# MainBoard.net
KiCad netlist of a schematic drawn in Altium Designer
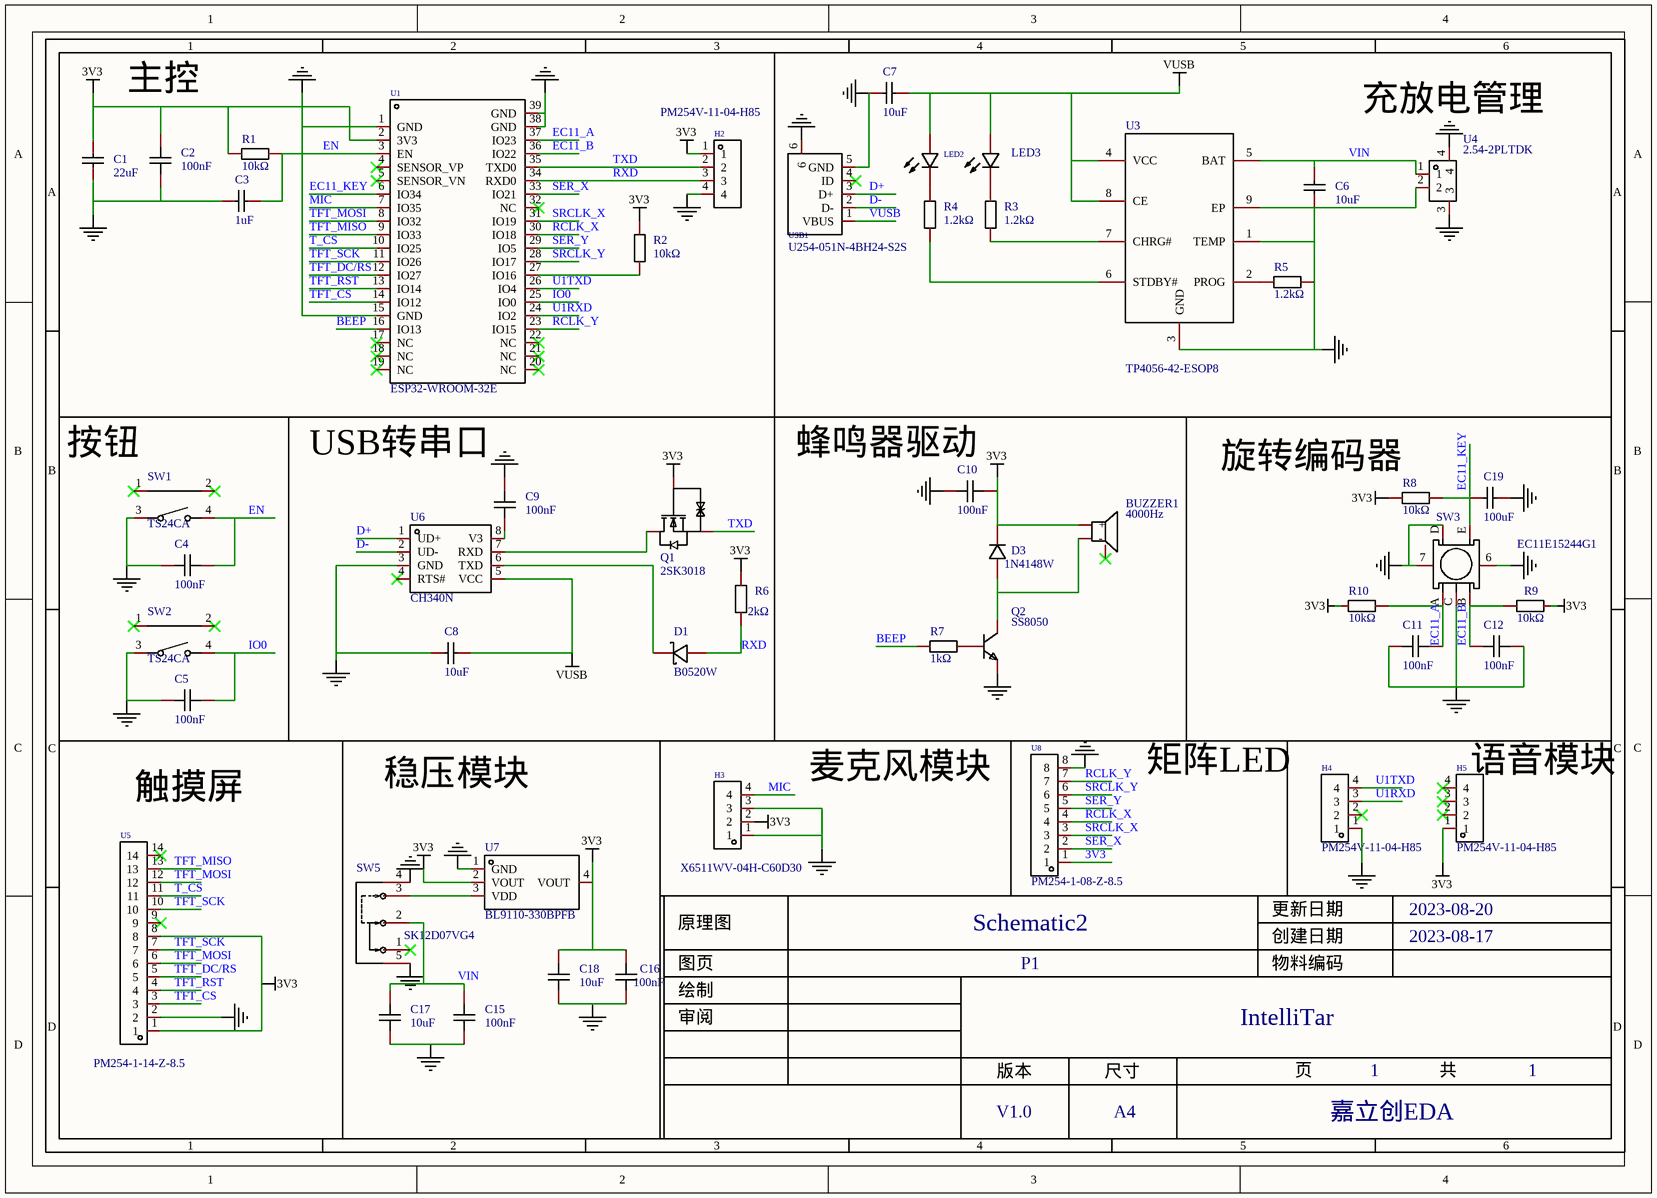
[diagram p0: MainBoard.schdoc]

(export (version "E")
  (design (tool "Eeschema 10.0.6"))
  (components
    (comp (ref "BUZZER1")
      (value "4000Hz")
      (description "驱动方式:无源(外部驱动);构造类型:电磁式;频率:4000Hz;长度:5.2mm;宽度:5.2mm;高度:2.5mm;")
      (fields
        (field (name "NAME") "4000Hz")
        (field (name "MANUFACTURER") "华能")
        (field (name "MANUFACTURER PART") "MLT-5020")
      )
      (libsource (lib "altium-import") (part "root_0_MLT-5020_"))
    )
    (comp (ref "C1")
      (value "22uF")
      (description "容值:22uF;精度:±10%;额定电压:25V;材质(温度系数):X5R;")
      (fields
        (field (name "NAME") "22uF")
        (field (name "MANUFACTURER") "SAMSUNG(三星)")
        (field (name "MANUFACTURER PART") "CL31A226KAHNNNE")
      )
      (libsource (lib "altium-import") (part "root_1_CL31A226KAHNNNE_"))
    )
    (comp (ref "C2")
      (value "100nF")
      (description "容值:100nF;精度:±10%;额定电压:50V;材质(温度系数):X7R;")
      (fields
        (field (name "NAME") "100nF")
        (field (name "MANUFACTURER") "YAGEO(国巨)")
        (field (name "MANUFACTURER PART") "CC0603KRX7R9BB104")
      )
      (libsource (lib "altium-import") (part "root_1_CC0603KRX7R9BB104_"))
    )
    (comp (ref "C3")
      (value "1uF")
      (description "容值:1uF;精度:±10%;额定电压:50V;材质(温度系数):X5R;")
      (fields
        (field (name "NAME") "1uF")
        (field (name "MANUFACTURER") "SAMSUNG(三星)")
        (field (name "MANUFACTURER PART") "CL10A105KB8NNNC")
      )
      (libsource (lib "altium-import") (part "root_0_CL10A105KB8NNNC_"))
    )
    (comp (ref "C4")
      (value "100nF")
      (description "容值:100nF;精度:±10%;额定电压:50V;材质(温度系数):X7R;")
      (fields
        (field (name "NAME") "100nF")
        (field (name "MANUFACTURER") "YAGEO(国巨)")
        (field (name "MANUFACTURER PART") "CC0603KRX7R9BB104")
      )
      (libsource (lib "altium-import") (part "root_0_CC0603KRX7R9BB104_"))
    )
    (comp (ref "C5")
      (value "100nF")
      (description "容值:100nF;精度:±10%;额定电压:50V;材质(温度系数):X7R;")
      (fields
        (field (name "NAME") "100nF")
        (field (name "MANUFACTURER") "YAGEO(国巨)")
        (field (name "MANUFACTURER PART") "CC0603KRX7R9BB104")
      )
      (libsource (lib "altium-import") (part "root_0_CC0603KRX7R9BB104_"))
    )
    (comp (ref "C6")
      (value "10uF")
      (description "容值:10uF;精度:±10%;额定电压:25V;材质(温度系数):X5R;")
      (fields
        (field (name "NAME") "10uF")
        (field (name "MANUFACTURER") "SAMSUNG(三星)")
        (field (name "MANUFACTURER PART") "CL21A106KAYNNNE")
      )
      (libsource (lib "altium-import") (part "root_3_CL21A106KAYNNNE_C15850_"))
    )
    (comp (ref "C7")
      (value "10uF")
      (description "容值:10uF;精度:±10%;额定电压:25V;材质(温度系数):X5R;")
      (fields
        (field (name "NAME") "10uF")
        (field (name "MANUFACTURER") "SAMSUNG(三星)")
        (field (name "MANUFACTURER PART") "CL21A106KAYNNNE")
      )
      (libsource (lib "altium-import") (part "root_0_CL21A106KAYNNNE_C15850_"))
    )
    (comp (ref "C8")
      (value "10uF")
      (description "容值:10uF;精度:±10%;额定电压:25V;材质(温度系数):X5R;")
      (fields
        (field (name "NAME") "10uF")
        (field (name "MANUFACTURER") "SAMSUNG(三星)")
        (field (name "MANUFACTURER PART") "CL21A106KAYNNNE")
      )
      (libsource (lib "altium-import") (part "root_0_CL21A106KAYNNNE_C15850_"))
    )
    (comp (ref "C9")
      (value "100nF")
      (description "容值:100nF;精度:±10%;额定电压:50V;材质(温度系数):X7R;")
      (fields
        (field (name "NAME") "100nF")
        (field (name "MANUFACTURER") "YAGEO(国巨)")
        (field (name "MANUFACTURER PART") "CC0603KRX7R9BB104")
      )
      (libsource (lib "altium-import") (part "root_1_CC0603KRX7R9BB104_"))
    )
    (comp (ref "C10")
      (value "100nF")
      (description "容值:100nF;精度:±10%;额定电压:50V;材质(温度系数):X7R;")
      (fields
        (field (name "NAME") "100nF")
        (field (name "MANUFACTURER") "YAGEO(国巨)")
        (field (name "MANUFACTURER PART") "CC0603KRX7R9BB104")
      )
      (libsource (lib "altium-import") (part "root_0_CC0603KRX7R9BB104_"))
    )
    (comp (ref "C11")
      (value "100nF")
      (description "容值:100nF;精度:±10%;额定电压:50V;材质(温度系数):X7R;")
      (fields
        (field (name "NAME") "100nF")
        (field (name "MANUFACTURER") "YAGEO(国巨)")
        (field (name "MANUFACTURER PART") "CC0603KRX7R9BB104")
      )
      (libsource (lib "altium-import") (part "root_2_CC0603KRX7R9BB104_"))
    )
    (comp (ref "C12")
      (value "100nF")
      (description "容值:100nF;精度:±10%;额定电压:50V;材质(温度系数):X7R;")
      (fields
        (field (name "NAME") "100nF")
        (field (name "MANUFACTURER") "YAGEO(国巨)")
        (field (name "MANUFACTURER PART") "CC0603KRX7R9BB104")
      )
      (libsource (lib "altium-import") (part "root_0_CC0603KRX7R9BB104_"))
    )
    (comp (ref "C15")
      (value "100nF")
      (description "容值:100nF;精度:±10%;额定电压:50V;材质(温度系数):X7R;")
      (fields
        (field (name "NAME") "100nF")
        (field (name "MANUFACTURER") "YAGEO(国巨)")
        (field (name "MANUFACTURER PART") "CC0603KRX7R9BB104")
      )
      (libsource (lib "altium-import") (part "root_1_CC0603KRX7R9BB104_"))
    )
    (comp (ref "C16")
      (value "100nF")
      (description "容值:100nF;精度:±10%;额定电压:50V;材质(温度系数):X7R;")
      (fields
        (field (name "NAME") "100nF")
        (field (name "MANUFACTURER") "YAGEO(国巨)")
        (field (name "MANUFACTURER PART") "CC0603KRX7R9BB104")
      )
      (libsource (lib "altium-import") (part "root_1_CC0603KRX7R9BB104_"))
    )
    (comp (ref "C17")
      (value "10uF")
      (description "容值:10uF;精度:±20%;额定电压:25V;材质(温度系数):X5R;")
      (fields
        (field (name "NAME") "10uF")
        (field (name "MANUFACTURER") "SAMSUNG(三星)")
        (field (name "MANUFACTURER PART") "CL10A106MA8NRNC")
      )
      (libsource (lib "altium-import") (part "root_1_CL10A106MA8NRNC_"))
    )
    (comp (ref "C18")
      (value "10uF")
      (description "容值:10uF;精度:±20%;额定电压:25V;材质(温度系数):X5R;")
      (fields
        (field (name "NAME") "10uF")
        (field (name "MANUFACTURER") "SAMSUNG(三星)")
        (field (name "MANUFACTURER PART") "CL10A106MA8NRNC")
      )
      (libsource (lib "altium-import") (part "root_1_CL10A106MA8NRNC_"))
    )
    (comp (ref "C19")
      (value "100uF")
      (description "容值:100uF;精度:±20%;额定电压:6.3V;材质(温度系数):X5R;")
      (fields
        (field (name "NAME") "100uF")
        (field (name "MANUFACTURER") "SAMSUNG(三星)")
        (field (name "MANUFACTURER PART") "CL31A107MQHNNNE")
      )
      (libsource (lib "altium-import") (part "root_0_CL31A107MQHNNNE_"))
    )
    (comp (ref "D1")
      (value "B0520W")
      (fields (field (name "NAME") "B0520W") (field (name "MANUFACTURER") "SHIKUES(时科)"))
      (libsource (lib "altium-import") (part "root_0_B0520W_C475609_"))
    )
    (comp (ref "D3")
      (value "1N4148W")
      (description "二极管配置:独立式;功率:400mW;直流反向耐压(Vr):75V;平均整流电流(Io):150mA;正向压降(Vf):1V@50mA;反向恢复时间(trr):4ns;")
      (fields (field (name "NAME") "1N4148W") (field (name "MANUFACTURER") "ST(先科)"))
      (libsource (lib "altium-import") (part "root_3_1N4148W_C81598_"))
    )
    (comp (ref "H2")
      (value "PM254V-11-04-H85")
      (description "排数:单排;总孔位数:4;间距:2.54mm;插孔结构:1x4P;行距:-;安装类型:直插;塑高:-;触头材质:黄铜;触头镀层:-;")
      (fields (field (name "NAME") "PM254V-11-04-H85") (field (name "MANUFACTURER") "XFCN(兴飞)"))
      (libsource (lib "altium-import") (part "root_0_PM254V-11-04-H85_"))
    )
    (comp (ref "H3")
      (value "X6511WV-04H-C60D30")
      (fields
        (field (name "NAME") "X6511WV-04H-C60D30")
        (field (name "MANUFACTURER") "XKB Connectivity(中国星坤)")
      )
      (libsource (lib "altium-import") (part "root_2_X6511WV-04H-C60D30_"))
    )
    (comp (ref "H4")
      (value "PM254V-11-04-H85")
      (description "排数:单排;总孔位数:4;间距:2.54mm;插孔结构:1x4P;行距:-;安装类型:直插;塑高:-;触头材质:黄铜;触头镀层:-;")
      (fields (field (name "NAME") "PM254V-11-04-H85") (field (name "MANUFACTURER") "XFCN(兴飞)"))
      (libsource (lib "altium-import") (part "root_2_PM254V-11-04-H85_"))
    )
    (comp (ref "H5")
      (value "PM254V-11-04-H85")
      (description "排数:单排;总孔位数:4;间距:2.54mm;插孔结构:1x4P;行距:-;安装类型:直插;塑高:-;触头材质:黄铜;触头镀层:-;")
      (fields (field (name "NAME") "PM254V-11-04-H85") (field (name "MANUFACTURER") "XFCN(兴飞)"))
      (libsource (lib "altium-import") (part "root_2_mirrored_PM254V-11-04-H85_"))
    )
    (comp (ref "LED2")
      (value "19-217/GHC-YR1S2/3T")
      (description "发光颜色:翠绿;二极管配置:-;主波长:520nm~535nm;色温:-;功率:110mW;安装方式:-;")
      (fields (field (name "MANUFACTURER") "EVERLIGHT(亿光)"))
      (libsource (lib "altium-import") (part "root_1_19-217/GHC-YR1S2/3T_"))
    )
    (comp (ref "LED3")
      (value "NCD0603R1")
      (description "发光颜色:红灯;")
      (fields (field (name "MANUFACTURER") "国星光电"))
      (libsource (lib "altium-import") (part "root_1_NCD0603R1_C84263_"))
    )
    (comp (ref "Q1")
      (value "2SK3018")
      (fields (field (name "NAME") "2SK3018") (field (name "MANUFACTURER") "TWGMC(台湾迪嘉)"))
      (libsource (lib "altium-import") (part "root_3_mirrored_2SK3018_"))
    )
    (comp (ref "Q2")
      (value "SS8050")
      (description "晶体管类型:NPN;集射极击穿电压(Vceo):25V;集电极电流(Ic):1.5A;功率(Pd):300mW;直流电流增益(hFE@Ic,Vce):200@100mA,1V;")
      (fields (field (name "NAME") "SS8050") (field (name "MANUFACTURER") "CJ(江苏长电/长晶)"))
      (libsource (lib "altium-import") (part "root_0_SS8050_C2150_"))
    )
    (comp (ref "R1")
      (value "10kΩ")
      (description "电阻类型:厚膜电阻;阻值:10kΩ;精度:±1%;功率:100mW;")
      (fields
        (field (name "NAME") "10kΩ")
        (field (name "MANUFACTURER") "UNI-ROYAL(厚声)")
        (field (name "MANUFACTURER PART") "0603WAF1002T5E")
      )
      (libsource (lib "altium-import") (part "root_0_0603WAF1002T5E_"))
    )
    (comp (ref "R2")
      (value "10kΩ")
      (description "电阻类型:厚膜电阻;阻值:10kΩ;精度:±1%;功率:100mW;")
      (fields
        (field (name "NAME") "10kΩ")
        (field (name "MANUFACTURER") "UNI-ROYAL(厚声)")
        (field (name "MANUFACTURER PART") "0603WAF1002T5E")
      )
      (libsource (lib "altium-import") (part "root_1_0603WAF1002T5E_"))
    )
    (comp (ref "R3")
      (value "1.2kΩ")
      (description "电阻类型:厚膜电阻;阻值:1.2kΩ;精度:±1%;功率:100mW;")
      (fields
        (field (name "NAME") "1.2kΩ")
        (field (name "MANUFACTURER") "UNI-ROYAL(厚声)")
        (field (name "MANUFACTURER PART") "0603WAF1201T5E")
      )
      (libsource (lib "altium-import") (part "root_1_0603WAF1201T5E_"))
    )
    (comp (ref "R4")
      (value "1.2kΩ")
      (description "电阻类型:厚膜电阻;阻值:1.2kΩ;精度:±1%;功率:100mW;")
      (fields
        (field (name "NAME") "1.2kΩ")
        (field (name "MANUFACTURER") "UNI-ROYAL(厚声)")
        (field (name "MANUFACTURER PART") "0603WAF1201T5E")
      )
      (libsource (lib "altium-import") (part "root_1_0603WAF1201T5E_"))
    )
    (comp (ref "R5")
      (value "1.2kΩ")
      (description "电阻类型:厚膜电阻;阻值:1.2kΩ;精度:±1%;功率:100mW;")
      (fields
        (field (name "NAME") "1.2kΩ")
        (field (name "MANUFACTURER") "UNI-ROYAL(厚声)")
        (field (name "MANUFACTURER PART") "0603WAF1201T5E")
      )
      (libsource (lib "altium-import") (part "root_0_0603WAF1201T5E_"))
    )
    (comp (ref "R6")
      (value "2kΩ")
      (description "电阻类型:厚膜电阻;阻值:2kΩ;精度:±1%;功率:100mW;")
      (fields
        (field (name "NAME") "2kΩ")
        (field (name "MANUFACTURER") "UNI-ROYAL(厚声)")
        (field (name "MANUFACTURER PART") "0603WAF2001T5E")
      )
      (libsource (lib "altium-import") (part "root_1_0603WAF2001T5E_"))
    )
    (comp (ref "R7")
      (value "1kΩ")
      (description "电阻类型:厚膜电阻;阻值:1kΩ;精度:±1%;功率:100mW;")
      (fields
        (field (name "NAME") "1kΩ")
        (field (name "MANUFACTURER") "UNI-ROYAL(厚声)")
        (field (name "MANUFACTURER PART") "0603WAF1001T5E")
      )
      (libsource (lib "altium-import") (part "root_0_0603WAF1001T5E_"))
    )
    (comp (ref "R8")
      (value "10kΩ")
      (description "电阻类型:厚膜电阻;阻值:10kΩ;精度:±1%;功率:100mW;")
      (fields
        (field (name "NAME") "10kΩ")
        (field (name "MANUFACTURER") "UNI-ROYAL(厚声)")
        (field (name "MANUFACTURER PART") "0603WAF1002T5E")
      )
      (libsource (lib "altium-import") (part "root_2_0603WAF1002T5E_"))
    )
    (comp (ref "R9")
      (value "10kΩ")
      (description "电阻类型:厚膜电阻;阻值:10kΩ;精度:±1%;功率:100mW;")
      (fields
        (field (name "NAME") "10kΩ")
        (field (name "MANUFACTURER") "UNI-ROYAL(厚声)")
        (field (name "MANUFACTURER PART") "0603WAF1002T5E")
      )
      (libsource (lib "altium-import") (part "root_0_0603WAF1002T5E_"))
    )
    (comp (ref "R10")
      (value "10kΩ")
      (description "电阻类型:厚膜电阻;阻值:10kΩ;精度:±1%;功率:100mW;")
      (fields
        (field (name "NAME") "10kΩ")
        (field (name "MANUFACTURER") "UNI-ROYAL(厚声)")
        (field (name "MANUFACTURER PART") "0603WAF1002T5E")
      )
      (libsource (lib "altium-import") (part "root_2_0603WAF1002T5E_"))
    )
    (comp (ref "SW1")
      (value "TS24CA")
      (description "触点电流:50mA;额定电压(DC):12V;电路结构:单刀单掷;安装方式:卧贴;带灯:-;机械寿命:-;")
      (fields (field (name "NAME") "TS24CA") (field (name "MANUFACTURER") "SHOU HAN(首韩)"))
      (libsource (lib "altium-import") (part "root_0_TS24CA_"))
    )
    (comp (ref "SW2")
      (value "TS24CA")
      (description "触点电流:50mA;额定电压(DC):12V;电路结构:单刀单掷;安装方式:卧贴;带灯:-;机械寿命:-;")
      (fields (field (name "NAME") "TS24CA") (field (name "MANUFACTURER") "SHOU HAN(首韩)"))
      (libsource (lib "altium-import") (part "root_0_TS24CA_"))
    )
    (comp (ref "SW3")
      (value "EC11E15244G1")
      (fields (field (name "NAME") "EC11E15244G1") (field (name "MANUFACTURER") "ALPSALPINE(阿尔卑斯阿尔派)"))
      (libsource (lib "altium-import") (part "root_0_EC11E15244G1_"))
    )
    (comp (ref "SW5")
      (value "SK12D07VG4")
      (description "额定电压 DC:50V;触点额定电流:500mA @ 50VDC;电路结构:SPDT;额定电压 AC:-;开关功能:On-On;")
      (fields (field (name "NAME") "SK12D07VG4") (field (name "MANUFACTURER") "SHOU HAN(首韩)"))
      (libsource (lib "altium-import") (part "root_1_SK12D07VG4_"))
    )
    (comp (ref "U1")
      (value "ESP32-WROOM-32E")
      (fields (field (name "NAME") "ESP32-WROOM-32E") (field (name "MANUFACTURER") "ESPRESSIF(乐鑫)"))
      (libsource (lib "altium-import") (part "root_0_ESP32-WROOM-32E_"))
    )
    (comp (ref "U3")
      (value "TP4056-42-ESOP8")
      (description "锂电池充电芯片")
      (fields (field (name "NAME") "TP4056-42-ESOP8") (field (name "MANUFACTURER") "TOPPOWER(南京拓微)"))
      (libsource (lib "altium-import") (part "root_0_TP4056-42-ESOP8_"))
    )
    (comp (ref "U4")
      (value "2.54-2PLTDK")
      (description "间距:2.5mm;插针结构:1x2P;排数:1;每排PIN数:2;公母:公型插针;安装方式:立贴;额定电流:3A;工作温度范围:-25℃~+85℃;")
      (fields (field (name "NAME") "2.54-2PLTDK") (field (name "MANUFACTURER") "SHOU HAN(首韩)"))
      (libsource (lib "altium-import") (part "root_0_2.54-2PLTDK_"))
    )
    (comp (ref "U5")
      (value "PM254-1-14-Z-8.5")
      (fields (field (name "NAME") "PM254-1-14-Z-8.5") (field (name "MANUFACTURER") "HCTL(华灿天禄)"))
      (libsource (lib "altium-import") (part "root_2_PM254-1-14-Z-8.5_"))
    )
    (comp (ref "U6")
      (value "CH340N")
      (description "应用功能:-;接口协议:-;")
      (fields (field (name "NAME") "CH340N") (field (name "MANUFACTURER") "WCH(南京沁恒)"))
      (libsource (lib "altium-import") (part "root_0_CH340N_C506813_"))
    )
    (comp (ref "U7")
      (value "BL9110-330BPFB")
      (description "输出类型:固定;输出极性:正;最大输入电压:6V;输出电压:3.3V;输出电流:1A;电源纹波抑制比(PSRR):70dB@(1kHz);")
      (fields (field (name "NAME") "BL9110-330BPFB") (field (name "MANUFACTURER") "BL(上海贝岭)"))
      (libsource (lib "altium-import") (part "root_0_BL9110-330BPFB_"))
    )
    (comp (ref "U8")
      (value "PM254-1-08-Z-8.5")
      (fields (field (name "NAME") "PM254-1-08-Z-8.5") (field (name "MANUFACTURER") "HCTL(华灿天禄)"))
      (libsource (lib "altium-import") (part "root_2_PM254-1-08-Z-8.5_"))
    )
    (comp (ref "USB1")
      (value "U254-051N-4BH24-S2S")
      (fields
        (field (name "NAME") "U254-051N-4BH24-S2S")
        (field (name "MANUFACTURER") "XKB Connectivity(中国星坤)")
      )
      (libsource (lib "altium-import") (part "root_2_U254-051N-4BH24-S2S_"))
    )
  )
  (nets
    (net (code "1") (name "/BEEP") (class "Default")
      (node (ref "R7") (pin "1") (pinfunction "1_1") (pintype "passive"))
      (node (ref "U1") (pin "16") (pinfunction "IO13_16") (pintype "passive"))
    )
    (net (code "2") (name "/D+") (class "Default")
      (node (ref "U6") (pin "1") (pinfunction "UD+_1") (pintype "passive"))
      (node (ref "USB1") (pin "3") (pinfunction "D+_3") (pintype "passive"))
    )
    (net (code "3") (name "/D-") (class "Default")
      (node (ref "U6") (pin "2") (pinfunction "UD-_2") (pintype "passive"))
      (node (ref "USB1") (pin "2") (pinfunction "D-_2") (pintype "passive"))
    )
    (net (code "4") (name "/EC11_A") (class "Default")
      (node (ref "C11") (pin "1") (pinfunction "1_1") (pintype "passive"))
      (node (ref "R10") (pin "1") (pinfunction "1_1") (pintype "passive"))
      (node (ref "SW3") (pin "A") (pinfunction "A_A") (pintype "passive"))
      (node (ref "U1") (pin "37") (pinfunction "IO23_37") (pintype "passive"))
    )
    (net (code "5") (name "/EC11_B") (class "Default")
      (node (ref "C12") (pin "1") (pinfunction "1_1") (pintype "passive"))
      (node (ref "R9") (pin "1") (pinfunction "1_1") (pintype "passive"))
      (node (ref "SW3") (pin "B") (pinfunction "B_B") (pintype "passive"))
      (node (ref "U1") (pin "36") (pinfunction "IO22_36") (pintype "passive"))
    )
    (net (code "6") (name "/EC11_KEY") (class "Default")
      (node (ref "C19") (pin "1") (pinfunction "1_1") (pintype "passive"))
      (node (ref "R8") (pin "1") (pinfunction "1_1") (pintype "passive"))
      (node (ref "SW3") (pin "E") (pinfunction "E_E") (pintype "passive"))
      (node (ref "U1") (pin "6") (pinfunction "IO34_6") (pintype "passive"))
    )
    (net (code "7") (name "/EN") (class "Default")
      (node (ref "C3") (pin "2") (pinfunction "2_2") (pintype "passive"))
      (node (ref "C4") (pin "2") (pinfunction "2_2") (pintype "passive"))
      (node (ref "R1") (pin "2") (pinfunction "2_2") (pintype "passive"))
      (node (ref "SW1") (pin "4") (pinfunction "4_4") (pintype "passive"))
      (node (ref "U1") (pin "3") (pinfunction "EN_3") (pintype "passive"))
    )
    (net (code "8") (name "/IO0") (class "Default")
      (node (ref "C5") (pin "2") (pinfunction "2_2") (pintype "passive"))
      (node (ref "SW2") (pin "4") (pinfunction "4_4") (pintype "passive"))
      (node (ref "U1") (pin "25") (pinfunction "IO0_25") (pintype "passive"))
    )
    (net (code "9") (name "/MIC") (class "Default")
      (node (ref "H3") (pin "4") (pinfunction "4_4") (pintype "passive"))
      (node (ref "U1") (pin "7") (pinfunction "IO35_7") (pintype "passive"))
    )
    (net (code "10") (name "/RCLK_X") (class "Default")
      (node (ref "U1") (pin "30") (pinfunction "IO18_30") (pintype "passive"))
      (node (ref "U8") (pin "4") (pinfunction "4_4") (pintype "passive"))
    )
    (net (code "11") (name "/RCLK_Y") (class "Default")
      (node (ref "U1") (pin "23") (pinfunction "IO15_23") (pintype "passive"))
      (node (ref "U8") (pin "7") (pinfunction "7_7") (pintype "passive"))
    )
    (net (code "12") (name "/RXD") (class "Default")
      (node (ref "D1") (pin "2") (pinfunction "A_2") (pintype "passive"))
      (node (ref "H2") (pin "3") (pinfunction "3_3") (pintype "passive"))
      (node (ref "R6") (pin "1") (pinfunction "1_1") (pintype "passive"))
      (node (ref "U1") (pin "34") (pinfunction "RXD0_34") (pintype "passive"))
    )
    (net (code "13") (name "/SER_X") (class "Default")
      (node (ref "U1") (pin "33") (pinfunction "IO21_33") (pintype "passive"))
      (node (ref "U8") (pin "2") (pinfunction "2_2") (pintype "passive"))
    )
    (net (code "14") (name "/SER_Y") (class "Default")
      (node (ref "U1") (pin "29") (pinfunction "IO5_29") (pintype "passive"))
      (node (ref "U8") (pin "5") (pinfunction "5_5") (pintype "passive"))
    )
    (net (code "15") (name "/SRCLK_X") (class "Default")
      (node (ref "U1") (pin "31") (pinfunction "IO19_31") (pintype "passive"))
      (node (ref "U8") (pin "3") (pinfunction "3_3") (pintype "passive"))
    )
    (net (code "16") (name "/SRCLK_Y") (class "Default")
      (node (ref "U1") (pin "28") (pinfunction "IO17_28") (pintype "passive"))
      (node (ref "U8") (pin "6") (pinfunction "6_6") (pintype "passive"))
    )
    (net (code "17") (name "/TFT_CS") (class "Default")
      (node (ref "U1") (pin "14") (pinfunction "IO12_14") (pintype "passive"))
      (node (ref "U5") (pin "3") (pinfunction "3_3") (pintype "passive"))
    )
    (net (code "18") (name "/TFT_DC{slash}RS") (class "Default")
      (node (ref "U1") (pin "12") (pinfunction "IO27_12") (pintype "passive"))
      (node (ref "U5") (pin "5") (pinfunction "5_5") (pintype "passive"))
    )
    (net (code "19") (name "/TFT_MISO") (class "Default")
      (node (ref "U1") (pin "9") (pinfunction "IO33_9") (pintype "passive"))
      (node (ref "U5") (pin "13") (pinfunction "13_13") (pintype "passive"))
    )
    (net (code "20") (name "/TFT_MOSI") (class "Default")
      (node (ref "U1") (pin "8") (pinfunction "IO32_8") (pintype "passive"))
      (node (ref "U5") (pin "12") (pinfunction "12_12") (pintype "passive"))
      (node (ref "U5") (pin "6") (pinfunction "6_6") (pintype "passive"))
    )
    (net (code "21") (name "/TFT_RST") (class "Default")
      (node (ref "U1") (pin "13") (pinfunction "IO14_13") (pintype "passive"))
      (node (ref "U5") (pin "4") (pinfunction "4_4") (pintype "passive"))
    )
    (net (code "22") (name "/TFT_SCK") (class "Default")
      (node (ref "U1") (pin "11") (pinfunction "IO26_11") (pintype "passive"))
      (node (ref "U5") (pin "10") (pinfunction "10_10") (pintype "passive"))
      (node (ref "U5") (pin "7") (pinfunction "7_7") (pintype "passive"))
    )
    (net (code "23") (name "/TXD") (class "Default")
      (node (ref "H2") (pin "2") (pinfunction "2_2") (pintype "passive"))
      (node (ref "Q1") (pin "2") (pinfunction "S_2") (pintype "passive"))
      (node (ref "U1") (pin "35") (pinfunction "TXD0_35") (pintype "passive"))
    )
    (net (code "24") (name "/T_CS") (class "Default")
      (node (ref "U1") (pin "10") (pinfunction "IO25_10") (pintype "passive"))
      (node (ref "U5") (pin "11") (pinfunction "11_11") (pintype "passive"))
    )
    (net (code "25") (name "/U1RXD") (class "Default")
      (node (ref "H4") (pin "3") (pinfunction "3_3") (pintype "passive"))
      (node (ref "U1") (pin "24") (pinfunction "IO2_24") (pintype "passive"))
    )
    (net (code "26") (name "/U1TXD") (class "Default")
      (node (ref "H4") (pin "4") (pinfunction "4_4") (pintype "passive"))
      (node (ref "U1") (pin "26") (pinfunction "IO4_26") (pintype "passive"))
    )
    (net (code "27") (name "/VIN") (class "Default")
      (node (ref "C15") (pin "2") (pinfunction "2_2") (pintype "passive"))
      (node (ref "C17") (pin "2") (pinfunction "2_2") (pintype "passive"))
      (node (ref "C6") (pin "1") (pinfunction "1_1") (pintype "passive"))
      (node (ref "SW5") (pin "2") (pinfunction "2_2") (pintype "passive"))
      (node (ref "U3") (pin "5") (pinfunction "BAT_5") (pintype "passive"))
      (node (ref "U4") (pin "1") (pinfunction "1_1") (pintype "passive"))
    )
    (net (code "28") (name "3V3") (class "Default")
      (node (ref "BUZZER1") (pin "1") (pinfunction "+_1") (pintype "passive"))
      (node (ref "C1") (pin "2") (pinfunction "2_2") (pintype "passive"))
      (node (ref "C10") (pin "2") (pinfunction "2_2") (pintype "passive"))
      (node (ref "C16") (pin "2") (pinfunction "2_2") (pintype "passive"))
      (node (ref "C18") (pin "2") (pinfunction "2_2") (pintype "passive"))
      (node (ref "C2") (pin "2") (pinfunction "2_2") (pintype "passive"))
      (node (ref "D3") (pin "1") (pinfunction "K_1") (pintype "passive"))
      (node (ref "H2") (pin "1") (pinfunction "1_1") (pintype "passive"))
      (node (ref "H3") (pin "2") (pinfunction "2_2") (pintype "passive"))
      (node (ref "H5") (pin "1") (pinfunction "1_1") (pintype "passive"))
      (node (ref "Q1") (pin "1") (pinfunction "G_1") (pintype "passive"))
      (node (ref "R1") (pin "1") (pinfunction "1_1") (pintype "passive"))
      (node (ref "R10") (pin "2") (pinfunction "2_2") (pintype "passive"))
      (node (ref "R2") (pin "2") (pinfunction "2_2") (pintype "passive"))
      (node (ref "R6") (pin "2") (pinfunction "2_2") (pintype "passive"))
      (node (ref "R8") (pin "2") (pinfunction "2_2") (pintype "passive"))
      (node (ref "R9") (pin "2") (pinfunction "2_2") (pintype "passive"))
      (node (ref "U1") (pin "2") (pinfunction "3V3_2") (pintype "passive"))
      (node (ref "U5") (pin "1") (pinfunction "1_1") (pintype "passive"))
      (node (ref "U5") (pin "8") (pinfunction "8_8") (pintype "passive"))
      (node (ref "U7") (pin "2") (pinfunction "VOUT_2") (pintype "passive"))
      (node (ref "U7") (pin "4") (pinfunction "VOUT_4") (pintype "passive"))
      (node (ref "U8") (pin "1") (pinfunction "1_1") (pintype "passive"))
    )
    (net (code "29") (name "<NO NET>") (class "Default")
      (node (ref "C1") (pin "1") (pinfunction "1_1") (pintype "passive"))
      (node (ref "C10") (pin "1") (pinfunction "1_1") (pintype "passive"))
      (node (ref "C11") (pin "2") (pinfunction "2_2") (pintype "passive"))
      (node (ref "C12") (pin "2") (pinfunction "2_2") (pintype "passive"))
      (node (ref "C15") (pin "1") (pinfunction "1_1") (pintype "passive"))
      (node (ref "C16") (pin "1") (pinfunction "1_1") (pintype "passive"))
      (node (ref "C17") (pin "1") (pinfunction "1_1") (pintype "passive"))
      (node (ref "C18") (pin "1") (pinfunction "1_1") (pintype "passive"))
      (node (ref "C19") (pin "2") (pinfunction "2_2") (pintype "passive"))
      (node (ref "C2") (pin "1") (pinfunction "1_1") (pintype "passive"))
      (node (ref "C3") (pin "1") (pinfunction "1_1") (pintype "passive"))
      (node (ref "C4") (pin "1") (pinfunction "1_1") (pintype "passive"))
      (node (ref "C5") (pin "1") (pinfunction "1_1") (pintype "passive"))
      (node (ref "C6") (pin "2") (pinfunction "2_2") (pintype "passive"))
      (node (ref "C7") (pin "1") (pinfunction "1_1") (pintype "passive"))
      (node (ref "C8") (pin "1") (pinfunction "1_1") (pintype "passive"))
      (node (ref "C9") (pin "2") (pinfunction "2_2") (pintype "passive"))
      (node (ref "H2") (pin "4") (pinfunction "4_4") (pintype "passive"))
      (node (ref "H3") (pin "1") (pinfunction "1_1") (pintype "passive"))
      (node (ref "H3") (pin "3") (pinfunction "3_3") (pintype "passive"))
      (node (ref "H4") (pin "1") (pinfunction "1_1") (pintype "passive"))
      (node (ref "Q2") (pin "2") (pinfunction "E_2") (pintype "passive"))
      (node (ref "R5") (pin "2") (pinfunction "2_2") (pintype "passive"))
      (node (ref "SW1") (pin "3") (pinfunction "3_3") (pintype "passive"))
      (node (ref "SW2") (pin "3") (pinfunction "3_3") (pintype "passive"))
      (node (ref "SW3") (pin "6") (pinfunction "6_6") (pintype "passive"))
      (node (ref "SW3") (pin "7") (pinfunction "7_7") (pintype "passive"))
      (node (ref "SW3") (pin "C") (pinfunction "C_C") (pintype "passive"))
      (node (ref "SW3") (pin "D") (pinfunction "D_D") (pintype "passive"))
      (node (ref "SW5") (pin "4") (pinfunction "4_4") (pintype "passive"))
      (node (ref "SW5") (pin "5") (pinfunction "5_5") (pintype "passive"))
      (node (ref "U1") (pin "1") (pinfunction "GND_1") (pintype "passive"))
      (node (ref "U1") (pin "15") (pinfunction "GND_15") (pintype "passive"))
      (node (ref "U1") (pin "38") (pinfunction "GND_38") (pintype "passive"))
      (node (ref "U1") (pin "39") (pinfunction "GND_39") (pintype "passive"))
      (node (ref "U3") (pin "1") (pinfunction "TEMP_1") (pintype "passive"))
      (node (ref "U3") (pin "3") (pinfunction "GND_3") (pintype "passive"))
      (node (ref "U3") (pin "9") (pinfunction "EP_9") (pintype "passive"))
      (node (ref "U4") (pin "2") (pinfunction "2_2") (pintype "passive"))
      (node (ref "U4") (pin "3") (pinfunction "3_3") (pintype "passive"))
      (node (ref "U4") (pin "4") (pinfunction "4_4") (pintype "passive"))
      (node (ref "U5") (pin "2") (pinfunction "2_2") (pintype "passive"))
      (node (ref "U6") (pin "3") (pinfunction "GND_3") (pintype "passive"))
      (node (ref "U7") (pin "1") (pinfunction "GND_1") (pintype "passive"))
      (node (ref "U8") (pin "8") (pinfunction "8_8") (pintype "passive"))
      (node (ref "USB1") (pin "5") (pinfunction "GND_5") (pintype "passive"))
      (node (ref "USB1") (pin "6") (pinfunction "6_6") (pintype "passive"))
    )
    (net (code "30") (name "Net-(BUZZER1--)") (class "Default")
      (node (ref "BUZZER1") (pin "2") (pinfunction "-_2") (pintype "passive"))
      (node (ref "D3") (pin "2") (pinfunction "A_2") (pintype "passive"))
      (node (ref "Q2") (pin "3") (pinfunction "C_3") (pintype "passive"))
    )
    (net (code "31") (name "Net-(D1-C)") (class "Default")
      (node (ref "D1") (pin "1") (pinfunction "C_1") (pintype "passive"))
      (node (ref "U6") (pin "6") (pinfunction "TXD_6") (pintype "passive"))
    )
    (net (code "32") (name "Net-(LED2-C)") (class "Default")
      (node (ref "LED2") (pin "1") (pinfunction "C_1") (pintype "passive"))
      (node (ref "R4") (pin "2") (pinfunction "2_2") (pintype "passive"))
    )
    (net (code "33") (name "Net-(LED3-K)") (class "Default")
      (node (ref "LED3") (pin "1") (pinfunction "K_1") (pintype "passive"))
      (node (ref "R3") (pin "2") (pinfunction "2_2") (pintype "passive"))
    )
    (net (code "34") (name "Net-(Q1-D)") (class "Default")
      (node (ref "Q1") (pin "3") (pinfunction "D_3") (pintype "passive"))
      (node (ref "U6") (pin "7") (pinfunction "RXD_7") (pintype "passive"))
    )
    (net (code "35") (name "Net-(Q2-B)") (class "Default")
      (node (ref "Q2") (pin "1") (pinfunction "B_1") (pintype "passive"))
      (node (ref "R7") (pin "2") (pinfunction "2_2") (pintype "passive"))
    )
    (net (code "36") (name "Net-(U1-IO16)") (class "Default")
      (node (ref "R2") (pin "1") (pinfunction "1_1") (pintype "passive"))
      (node (ref "U1") (pin "27") (pinfunction "IO16_27") (pintype "passive"))
    )
    (net (code "37") (name "Net-(U3-CHRG#)") (class "Default")
      (node (ref "R3") (pin "1") (pinfunction "1_1") (pintype "passive"))
      (node (ref "U3") (pin "7") (pinfunction "CHRG#_7") (pintype "passive"))
    )
    (net (code "38") (name "Net-(U3-PROG)") (class "Default")
      (node (ref "R5") (pin "1") (pinfunction "1_1") (pintype "passive"))
      (node (ref "U3") (pin "2") (pinfunction "PROG_2") (pintype "passive"))
    )
    (net (code "39") (name "Net-(U3-STDBY#)") (class "Default")
      (node (ref "R4") (pin "1") (pinfunction "1_1") (pintype "passive"))
      (node (ref "U3") (pin "6") (pinfunction "STDBY#_6") (pintype "passive"))
    )
    (net (code "40") (name "Net-(U6-V3)") (class "Default")
      (node (ref "C9") (pin "1") (pinfunction "1_1") (pintype "passive"))
      (node (ref "U6") (pin "8") (pinfunction "V3_8") (pintype "passive"))
    )
    (net (code "41") (name "Net-(U7-VDD)") (class "Default")
      (node (ref "SW5") (pin "3") (pinfunction "3_3") (pintype "passive"))
      (node (ref "U7") (pin "3") (pinfunction "VDD_3") (pintype "passive"))
    )
    (net (code "42") (name "VUSB") (class "Default")
      (node (ref "C7") (pin "2") (pinfunction "2_2") (pintype "passive"))
      (node (ref "C8") (pin "2") (pinfunction "2_2") (pintype "passive"))
      (node (ref "LED2") (pin "2") (pinfunction "A_2") (pintype "passive"))
      (node (ref "LED3") (pin "2") (pinfunction "A_2") (pintype "passive"))
      (node (ref "U3") (pin "4") (pinfunction "VCC_4") (pintype "passive"))
      (node (ref "U3") (pin "8") (pinfunction "CE_8") (pintype "passive"))
      (node (ref "U6") (pin "5") (pinfunction "VCC_5") (pintype "passive"))
      (node (ref "USB1") (pin "1") (pinfunction "VBUS_1") (pintype "passive"))
    )
    (net (code "43") (name "unconnected-(BUZZER1-NC-Pad3)") (class "Default")
      (node (ref "BUZZER1") (pin "3") (pinfunction "NC_3") (pintype "passive+no_connect"))
    )
    (net (code "44") (name "unconnected-(H4-Pad2)") (class "Default")
      (node (ref "H4") (pin "2") (pinfunction "2_2") (pintype "passive+no_connect"))
    )
    (net (code "45") (name "unconnected-(H5-Pad2)") (class "Default")
      (node (ref "H5") (pin "2") (pinfunction "2_2") (pintype "passive+no_connect"))
    )
    (net (code "46") (name "unconnected-(H5-Pad3)") (class "Default")
      (node (ref "H5") (pin "3") (pinfunction "3_3") (pintype "passive+no_connect"))
    )
    (net (code "47") (name "unconnected-(H5-Pad4)") (class "Default")
      (node (ref "H5") (pin "4") (pinfunction "4_4") (pintype "passive+no_connect"))
    )
    (net (code "48") (name "unconnected-(SW1-Pad1)") (class "Default")
      (node (ref "SW1") (pin "1") (pinfunction "1_1") (pintype "passive+no_connect"))
    )
    (net (code "49") (name "unconnected-(SW1-Pad2)") (class "Default")
      (node (ref "SW1") (pin "2") (pinfunction "2_2") (pintype "passive+no_connect"))
    )
    (net (code "50") (name "unconnected-(SW2-Pad1)") (class "Default")
      (node (ref "SW2") (pin "1") (pinfunction "1_1") (pintype "passive+no_connect"))
    )
    (net (code "51") (name "unconnected-(SW2-Pad2)") (class "Default")
      (node (ref "SW2") (pin "2") (pinfunction "2_2") (pintype "passive+no_connect"))
    )
    (net (code "52") (name "unconnected-(SW5-Pad1)") (class "Default")
      (node (ref "SW5") (pin "1") (pinfunction "1_1") (pintype "passive+no_connect"))
    )
    (net (code "53") (name "unconnected-(U1-NC-Pad17)") (class "Default")
      (node (ref "U1") (pin "17") (pinfunction "NC_17") (pintype "passive+no_connect"))
    )
    (net (code "54") (name "unconnected-(U1-NC-Pad18)") (class "Default")
      (node (ref "U1") (pin "18") (pinfunction "NC_18") (pintype "passive+no_connect"))
    )
    (net (code "55") (name "unconnected-(U1-NC-Pad19)") (class "Default")
      (node (ref "U1") (pin "19") (pinfunction "NC_19") (pintype "passive+no_connect"))
    )
    (net (code "56") (name "unconnected-(U1-NC-Pad20)") (class "Default")
      (node (ref "U1") (pin "20") (pinfunction "NC_20") (pintype "passive+no_connect"))
    )
    (net (code "57") (name "unconnected-(U1-NC-Pad21)") (class "Default")
      (node (ref "U1") (pin "21") (pinfunction "NC_21") (pintype "passive+no_connect"))
    )
    (net (code "58") (name "unconnected-(U1-NC-Pad22)") (class "Default")
      (node (ref "U1") (pin "22") (pinfunction "NC_22") (pintype "passive+no_connect"))
    )
    (net (code "59") (name "unconnected-(U1-NC-Pad32)") (class "Default")
      (node (ref "U1") (pin "32") (pinfunction "NC_32") (pintype "passive+no_connect"))
    )
    (net (code "60") (name "unconnected-(U1-SENSOR_VN-Pad5)") (class "Default")
      (node (ref "U1") (pin "5") (pinfunction "SENSOR_VN_5") (pintype "passive+no_connect"))
    )
    (net (code "61") (name "unconnected-(U1-SENSOR_VP-Pad4)") (class "Default")
      (node (ref "U1") (pin "4") (pinfunction "SENSOR_VP_4") (pintype "passive+no_connect"))
    )
    (net (code "62") (name "unconnected-(U5-Pad9)") (class "Default")
      (node (ref "U5") (pin "9") (pinfunction "9_9") (pintype "passive+no_connect"))
    )
    (net (code "63") (name "unconnected-(U5-Pad14)") (class "Default")
      (node (ref "U5") (pin "14") (pinfunction "14_14") (pintype "passive+no_connect"))
    )
    (net (code "64") (name "unconnected-(U6-RTS#-Pad4)") (class "Default")
      (node (ref "U6") (pin "4") (pinfunction "RTS#_4") (pintype "passive+no_connect"))
    )
    (net (code "65") (name "unconnected-(USB1-ID-Pad4)") (class "Default")
      (node (ref "USB1") (pin "4") (pinfunction "ID_4") (pintype "passive+no_connect"))
    )
  )
)
